# esp8266.net
KiCad netlist of a schematic drawn in EAGLE
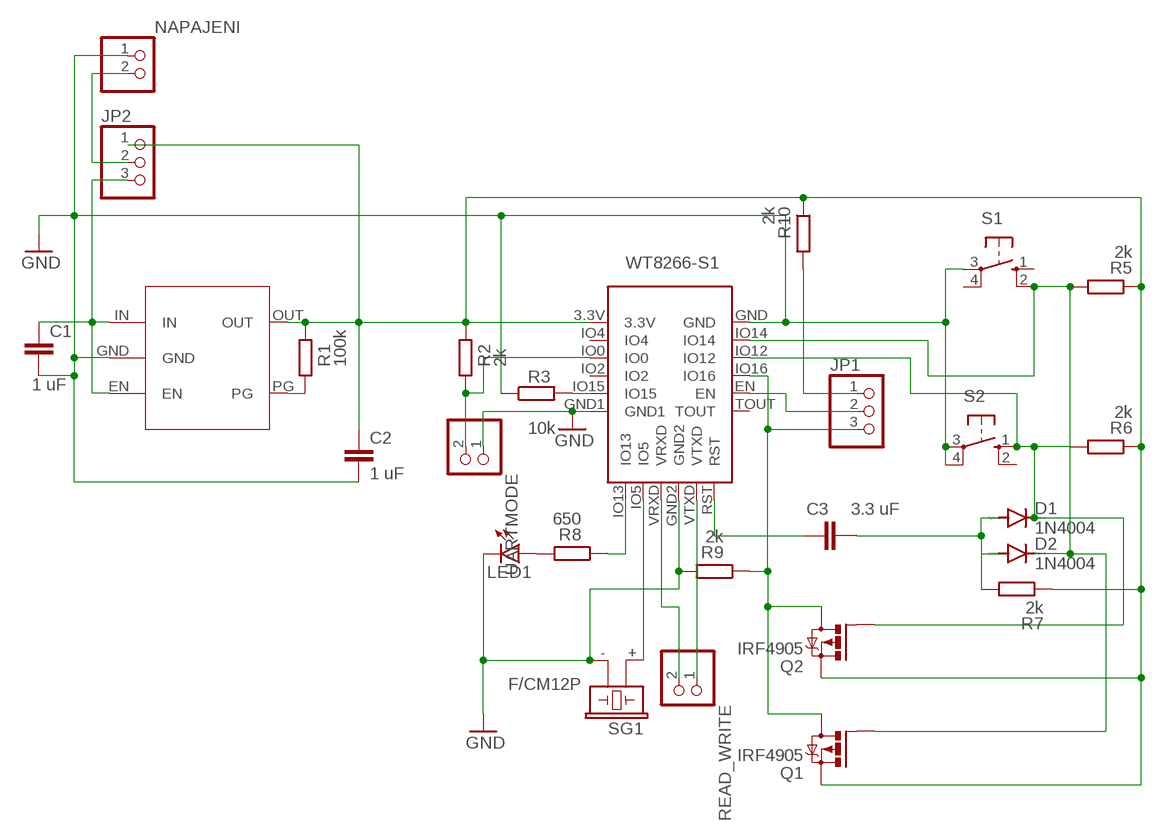
[diagram p0: schematic, sheet 1]

(export (version "E")
  (design (tool "Eeschema 10.0.6"))
  (components
    (comp (ref "C1")
      (value "1 uF")
      (footprint "eagle-import:C2.5-2")
      (libsource (lib "eagle-import") (part "C2.5/2"))
    )
    (comp (ref "C2")
      (value "1 uF")
      (footprint "eagle-import:C2.5-2")
      (libsource (lib "eagle-import") (part "C2.5/2"))
    )
    (comp (ref "C3")
      (value "3.3 uF")
      (footprint "eagle-import:C2.5-2")
      (libsource (lib "eagle-import") (part "C2.5/2"))
    )
    (comp (ref "D1")
      (value "1N4004")
      (footprint "eagle-import:DO41-10")
      (libsource (lib "eagle-import") (part "1N4004"))
    )
    (comp (ref "D2")
      (value "1N4004")
      (footprint "eagle-import:DO41-10")
      (libsource (lib "eagle-import") (part "1N4004"))
    )
    (comp (ref "JP1")
      (value "PINHD-1X3")
      (footprint "eagle-import:1X03")
      (libsource (lib "eagle-import") (part "PINHD-1X3"))
    )
    (comp (ref "JP2")
      (value "PINHD-1X3")
      (footprint "eagle-import:1X03")
      (libsource (lib "eagle-import") (part "PINHD-1X3"))
    )
    (comp (ref "LED1")
      (value "LED5MM")
      (footprint "eagle-import:LED5MM")
      (libsource (lib "eagle-import") (part "LED5MM"))
    )
    (comp (ref "NAPAJENI")
      (value "PINHD-1X2")
      (footprint "eagle-import:1X02")
      (libsource (lib "eagle-import") (part "PINHD-1X2"))
    )
    (comp (ref "Q1")
      (value "IRF4905")
      (footprint "eagle-import:TO220BH")
      (libsource (lib "eagle-import") (part "IRF4905"))
    )
    (comp (ref "Q2")
      (value "IRF4905")
      (footprint "eagle-import:TO220BH")
      (libsource (lib "eagle-import") (part "IRF4905"))
    )
    (comp (ref "R1")
      (value "100k")
      (footprint "eagle-import:0207_10")
      (libsource (lib "eagle-import") (part "R-EU_0207/10"))
    )
    (comp (ref "R2")
      (value "2k")
      (footprint "eagle-import:0207_10")
      (libsource (lib "eagle-import") (part "R-EU_0207/10"))
    )
    (comp (ref "R3")
      (value "10k")
      (footprint "eagle-import:0207_10")
      (libsource (lib "eagle-import") (part "R-EU_0207/10"))
    )
    (comp (ref "R5")
      (value "2k")
      (footprint "eagle-import:0207_10")
      (libsource (lib "eagle-import") (part "R-EU_0207/10"))
    )
    (comp (ref "R6")
      (value "2k")
      (footprint "eagle-import:0207_10")
      (libsource (lib "eagle-import") (part "R-EU_0207/10"))
    )
    (comp (ref "R7")
      (value "2k")
      (footprint "eagle-import:0207_10")
      (libsource (lib "eagle-import") (part "R-EU_0207/10"))
    )
    (comp (ref "R8")
      (value "650")
      (footprint "eagle-import:0207_10")
      (libsource (lib "eagle-import") (part "R-EU_0207/10"))
    )
    (comp (ref "R9")
      (value "2k")
      (footprint "eagle-import:0207_10")
      (libsource (lib "eagle-import") (part "R-EU_0207/10"))
    )
    (comp (ref "R10")
      (value "2k")
      (footprint "eagle-import:0207_10")
      (libsource (lib "eagle-import") (part "R-EU_0207/10"))
    )
    (comp (ref "READ_WRITE")
      (value "PINHD-1X2")
      (footprint "eagle-import:1X02")
      (libsource (lib "eagle-import") (part "PINHD-1X2"))
    )
    (comp (ref "S1")
      (value "10-XX")
      (footprint "eagle-import:B3F-10XX")
      (fields (field (name "MPN") "B3F-1000"))
      (libsource (lib "eagle-import") (part "10-XX"))
    )
    (comp (ref "S2")
      (value "10-XX")
      (footprint "eagle-import:B3F-10XX")
      (fields (field (name "MPN") "B3F-1000"))
      (libsource (lib "eagle-import") (part "10-XX"))
    )
    (comp (ref "SG1")
      (value "F/CM12P")
      (footprint "eagle-import:F_CM12P")
      (libsource (lib "eagle-import") (part "F/CM12P"))
    )
    (comp (ref "U$1")
      (value "WT8266-S1")
      (footprint "eagle-import:WT8266-S1")
      (libsource (lib "eagle-import") (part "WT8266-S1"))
    )
    (comp (ref "U$2")
      (value "LDLN030")
      (footprint "eagle-import:LDLN030")
      (libsource (lib "eagle-import") (part "LDLN030"))
    )
    (comp (ref "UARTMODE")
      (value "PINHD-1X2")
      (footprint "eagle-import:1X02")
      (libsource (lib "eagle-import") (part "PINHD-1X2"))
    )
  )
  (nets
    (net (code "1") (name "GND") (class "Default")
      (node (ref "C1") (pin "2") (pinfunction "2_2") (pintype "passive"))
      (node (ref "C2") (pin "2") (pinfunction "2_2") (pintype "passive"))
      (node (ref "LED1") (pin "K") (pinfunction "C_K") (pintype "passive"))
      (node (ref "NAPAJENI") (pin "1") (pinfunction "1_1") (pintype "passive"))
      (node (ref "R3") (pin "1") (pinfunction "1_1") (pintype "passive"))
      (node (ref "R9") (pin "2") (pinfunction "2_2") (pintype "passive"))
      (node (ref "S1") (pin "3") (pinfunction "P_3") (pintype "passive"))
      (node (ref "S2") (pin "3") (pinfunction "P_3") (pintype "passive"))
      (node (ref "S2") (pin "4") (pinfunction "P1_4") (pintype "passive"))
      (node (ref "SG1") (pin "-") (pinfunction "2_-") (pintype "passive"))
      (node (ref "U$1") (pin "GND") (pinfunction "GND_GND") (pintype "bidirectional"))
      (node (ref "U$1") (pin "GND1") (pinfunction "GND1_GND1") (pintype "bidirectional"))
      (node (ref "U$1") (pin "GND2") (pinfunction "GND2_GND2") (pintype "bidirectional"))
      (node (ref "U$2") (pin "GND") (pinfunction "GND_GND") (pintype "bidirectional"))
      (node (ref "UARTMODE") (pin "1") (pinfunction "1_1") (pintype "passive"))
    )
    (net (code "2") (name "Net-(C1-Pad1)") (class "Default")
      (node (ref "C1") (pin "1") (pinfunction "1_1") (pintype "passive"))
      (node (ref "JP2") (pin "3") (pinfunction "3_3") (pintype "passive"))
      (node (ref "U$2") (pin "EN") (pinfunction "EN_EN") (pintype "bidirectional"))
      (node (ref "U$2") (pin "IN") (pinfunction "IN_IN") (pintype "bidirectional"))
    )
    (net (code "3") (name "Net-(C2-Pad1)") (class "Default")
      (node (ref "C2") (pin "1") (pinfunction "1_1") (pintype "passive"))
      (node (ref "JP2") (pin "1") (pinfunction "1_1") (pintype "passive"))
      (node (ref "Q1") (pin "S") (pinfunction "S_S") (pintype "passive"))
      (node (ref "Q2") (pin "S") (pinfunction "S_S") (pintype "passive"))
      (node (ref "R1") (pin "2") (pinfunction "2_2") (pintype "passive"))
      (node (ref "R10") (pin "1") (pinfunction "1_1") (pintype "passive"))
      (node (ref "R2") (pin "2") (pinfunction "2_2") (pintype "passive"))
      (node (ref "R5") (pin "1") (pinfunction "1_1") (pintype "passive"))
      (node (ref "R6") (pin "1") (pinfunction "1_1") (pintype "passive"))
      (node (ref "R7") (pin "1") (pinfunction "1_1") (pintype "passive"))
      (node (ref "U$1") (pin "3.3V") (pinfunction "3.3V_3.3V") (pintype "bidirectional"))
      (node (ref "U$2") (pin "OUT") (pinfunction "OUT_OUT") (pintype "bidirectional"))
    )
    (net (code "4") (name "Net-(C3-Pad1)") (class "Default")
      (node (ref "C3") (pin "1") (pinfunction "1_1") (pintype "passive"))
      (node (ref "U$1") (pin "RST") (pinfunction "RST_RST") (pintype "bidirectional"))
    )
    (net (code "5") (name "Net-(C3-Pad2)") (class "Default")
      (node (ref "C3") (pin "2") (pinfunction "2_2") (pintype "passive"))
      (node (ref "D1") (pin "A") (pinfunction "A_A") (pintype "passive"))
      (node (ref "D2") (pin "A") (pinfunction "A_A") (pintype "passive"))
      (node (ref "R7") (pin "2") (pinfunction "2_2") (pintype "passive"))
    )
    (net (code "6") (name "Net-(JP1-Pad1)") (class "Default")
      (node (ref "JP1") (pin "1") (pinfunction "1_1") (pintype "passive"))
      (node (ref "R10") (pin "2") (pinfunction "2_2") (pintype "passive"))
    )
    (net (code "7") (name "Net-(JP1-Pad2)") (class "Default")
      (node (ref "JP1") (pin "2") (pinfunction "2_2") (pintype "passive"))
      (node (ref "U$1") (pin "EN") (pinfunction "EN_EN") (pintype "bidirectional"))
    )
    (net (code "8") (name "Net-(JP1-Pad3)") (class "Default")
      (node (ref "JP1") (pin "3") (pinfunction "3_3") (pintype "passive"))
      (node (ref "Q1") (pin "D") (pinfunction "D_D") (pintype "passive"))
      (node (ref "Q2") (pin "D") (pinfunction "D_D") (pintype "passive"))
      (node (ref "R9") (pin "1") (pinfunction "1_1") (pintype "passive"))
      (node (ref "U$1") (pin "IO16") (pinfunction "IO16_IO16") (pintype "bidirectional"))
    )
    (net (code "9") (name "Net-(JP2-Pad2)") (class "Default")
      (node (ref "JP2") (pin "2") (pinfunction "2_2") (pintype "passive"))
      (node (ref "NAPAJENI") (pin "2") (pinfunction "2_2") (pintype "passive"))
    )
    (net (code "10") (name "Net-(LED1-PadA)") (class "Default")
      (node (ref "LED1") (pin "A") (pinfunction "A_A") (pintype "passive"))
      (node (ref "R8") (pin "2") (pinfunction "2_2") (pintype "passive"))
    )
    (net (code "11") (name "Net-(R1-Pad1)") (class "Default")
      (node (ref "R1") (pin "1") (pinfunction "1_1") (pintype "passive"))
      (node (ref "U$2") (pin "PG") (pinfunction "PG_PG") (pintype "bidirectional"))
    )
    (net (code "12") (name "Net-(R2-Pad1)") (class "Default")
      (node (ref "R2") (pin "1") (pinfunction "1_1") (pintype "passive"))
      (node (ref "U$1") (pin "IO0") (pinfunction "IO0_IO0") (pintype "bidirectional"))
      (node (ref "UARTMODE") (pin "2") (pinfunction "2_2") (pintype "passive"))
    )
    (net (code "13") (name "Net-(R3-Pad2)") (class "Default")
      (node (ref "R3") (pin "2") (pinfunction "2_2") (pintype "passive"))
      (node (ref "U$1") (pin "IO15") (pinfunction "IO15_IO15") (pintype "bidirectional"))
    )
    (net (code "14") (name "Net-(R8-Pad1)") (class "Default")
      (node (ref "R8") (pin "1") (pinfunction "1_1") (pintype "passive"))
      (node (ref "U$1") (pin "IO13") (pinfunction "IO13_IO13") (pintype "bidirectional"))
    )
    (net (code "15") (name "Net-(READ_WRITE-Pad1)") (class "Default")
      (node (ref "READ_WRITE") (pin "1") (pinfunction "1_1") (pintype "passive"))
      (node (ref "U$1") (pin "VTXD") (pinfunction "VTXD_VTXD") (pintype "bidirectional"))
    )
    (net (code "16") (name "Net-(READ_WRITE-Pad2)") (class "Default")
      (node (ref "READ_WRITE") (pin "2") (pinfunction "2_2") (pintype "passive"))
      (node (ref "U$1") (pin "VRXD") (pinfunction "VRXD_VRXD") (pintype "bidirectional"))
    )
    (net (code "17") (name "Net-(S1-S1)") (class "Default")
      (node (ref "D2") (pin "C") (pinfunction "C_C") (pintype "passive"))
      (node (ref "Q1") (pin "G") (pinfunction "G_G") (pintype "passive"))
      (node (ref "R5") (pin "2") (pinfunction "2_2") (pintype "passive"))
      (node (ref "S1") (pin "2") (pinfunction "S1_2") (pintype "passive"))
      (node (ref "U$1") (pin "IO14") (pinfunction "IO14_IO14") (pintype "bidirectional"))
    )
    (net (code "18") (name "Net-(S2-S)") (class "Default")
      (node (ref "D1") (pin "C") (pinfunction "C_C") (pintype "passive"))
      (node (ref "Q2") (pin "G") (pinfunction "G_G") (pintype "passive"))
      (node (ref "R6") (pin "2") (pinfunction "2_2") (pintype "passive"))
      (node (ref "S2") (pin "1") (pinfunction "S_1") (pintype "passive"))
      (node (ref "U$1") (pin "IO12") (pinfunction "IO12_IO12") (pintype "bidirectional"))
    )
    (net (code "19") (name "Net-(SG1-1)") (class "Default")
      (node (ref "SG1") (pin "+") (pinfunction "1_+") (pintype "passive"))
      (node (ref "U$1") (pin "IO5") (pinfunction "IO5_IO5") (pintype "bidirectional"))
    )
    (net (code "20") (name "unconnected-(S1-P1-Pad4)") (class "Default")
      (node (ref "S1") (pin "4") (pinfunction "P1_4") (pintype "passive"))
    )
    (net (code "21") (name "unconnected-(S1-S-Pad1)") (class "Default")
      (node (ref "S1") (pin "1") (pinfunction "S_1") (pintype "passive"))
    )
    (net (code "22") (name "unconnected-(S2-S1-Pad2)") (class "Default")
      (node (ref "S2") (pin "2") (pinfunction "S1_2") (pintype "passive"))
    )
    (net (code "23") (name "unconnected-(U$1-PadIO2)") (class "Default")
      (node (ref "U$1") (pin "IO2") (pinfunction "IO2_IO2") (pintype "bidirectional"))
    )
    (net (code "24") (name "unconnected-(U$1-PadIO4)") (class "Default")
      (node (ref "U$1") (pin "IO4") (pinfunction "IO4_IO4") (pintype "bidirectional"))
    )
    (net (code "25") (name "unconnected-(U$1-PadTOUT)") (class "Default")
      (node (ref "U$1") (pin "TOUT") (pinfunction "TOUT_TOUT") (pintype "bidirectional"))
    )
  )
)
